# SCH_BMS.net
KiCad netlist of a schematic drawn in Altium Designer
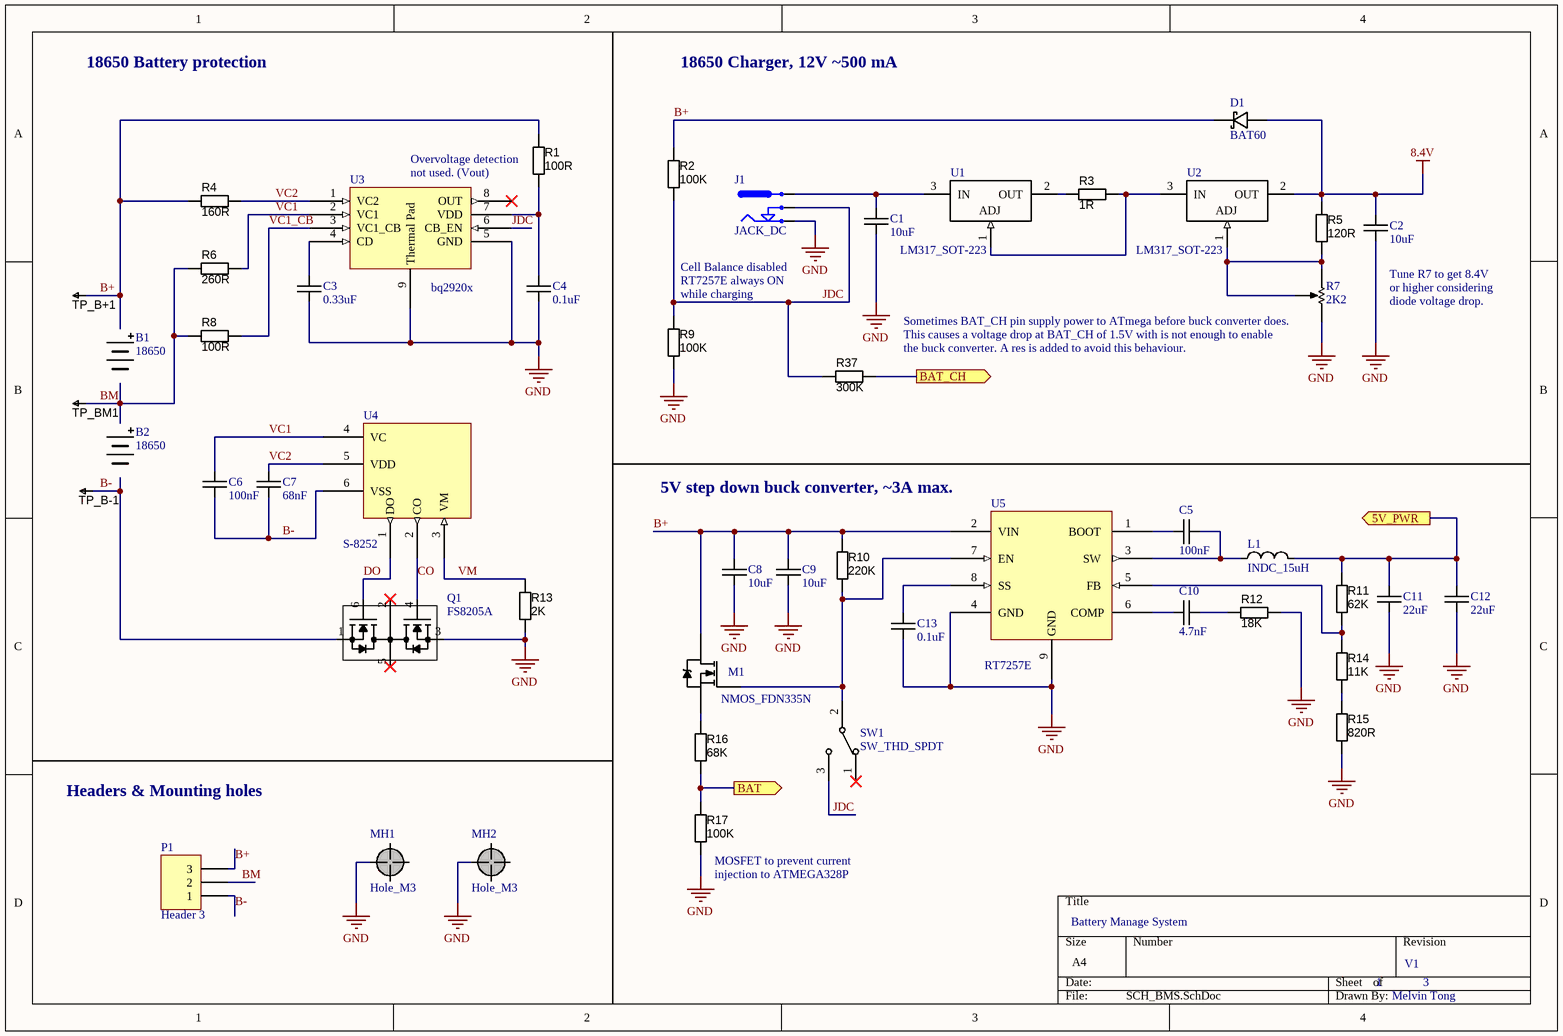
[diagram p0: SCH_BMS.SchDoc]

(export (version "E")
  (design (tool "Eeschema 10.0.6"))
  (components
    (comp (ref "B1") (value "18650") (libsource (lib "Schlib_Sword") (part "Battery_18650")))
    (comp (ref "B2") (value "18650") (libsource (lib "Schlib_Sword") (part "Battery_18650")))
    (comp (ref "C1")
      (value "10uF")
      (footprint "CAP_0805")
      (description "SMD 0805/1206")
      (libsource (lib "Schlib_Sword") (part "CAP_10uF"))
    )
    (comp (ref "C2")
      (value "10uF")
      (footprint "CAP_1206")
      (description "SMD 0805/1206")
      (libsource (lib "Schlib_Sword") (part "CAP_10uF"))
    )
    (comp (ref "C3")
      (value "0.33uF")
      (footprint "CAP_0805")
      (description "SMD 0805")
      (libsource (lib "Schlib_Sword") (part "CAP_330nF"))
    )
    (comp (ref "C4")
      (value "0.1uF")
      (footprint "CAP_0805")
      (description "SMD 0805")
      (libsource (lib "Schlib_Sword") (part "CAP_0.1uF"))
    )
    (comp (ref "C5")
      (value "100nF")
      (footprint "CAP_0805")
      (description "SMD 0805")
      (libsource (lib "Schlib_Sword") (part "CAP_100nF"))
    )
    (comp (ref "C6")
      (value "100nF")
      (footprint "CAP_0805")
      (description "SMD 0805")
      (libsource (lib "Schlib_Sword") (part "CAP_0.1uF"))
    )
    (comp (ref "C7")
      (value "68nF")
      (footprint "CAP_0805")
      (description "SMD 0805")
      (libsource (lib "Schlib_Sword") (part "CAP_0.1uF"))
    )
    (comp (ref "C8")
      (value "10uF")
      (footprint "CAP_1206")
      (description "SMD 0805/1206")
      (libsource (lib "Schlib_Sword") (part "CAP_10uF"))
    )
    (comp (ref "C9")
      (value "10uF")
      (footprint "CAP_1206")
      (description "SMD 0805/1206")
      (libsource (lib "Schlib_Sword") (part "CAP_10uF"))
    )
    (comp (ref "C10")
      (value "4.7nF")
      (footprint "CAP_0805")
      (description "SMD 0805")
      (libsource (lib "Schlib_Sword") (part "CAP_4.7nF"))
    )
    (comp (ref "C11")
      (value "22uF")
      (footprint "CAP_1206")
      (description "SMD 1206")
      (libsource (lib "Schlib_Sword") (part "CAP_22uF"))
    )
    (comp (ref "C12")
      (value "22uF")
      (footprint "CAP_1206")
      (description "SMD 1206")
      (libsource (lib "Schlib_Sword") (part "CAP_22uF"))
    )
    (comp (ref "C13")
      (value "0.1uF")
      (footprint "CAP_0805")
      (description "SMD 0805")
      (libsource (lib "Schlib_Sword") (part "CAP_0.1uF"))
    )
    (comp (ref "D1")
      (value "BAT60")
      (footprint "SOD323")
      (description "Schottky Diode 3A, Vf~0.24V, Vr=10V")
      (libsource (lib "Schlib_Sword") (part "BAT60"))
    )
    (comp (ref "J1") (value "JACK_DC") (footprint "DC-004") (libsource (lib "Schlib_Sword") (part "JACK_DC")))
    (comp (ref "L1")
      (value "INDC_15uH")
      (footprint "IND_15uH")
      (description "15uH ±20% 4.2A 28.4mΩ SMD,12.5x12.5x6.5mm Power Inductors")
      (libsource (lib "Schlib_Sword") (part "INDC_15uH"))
    )
    (comp (ref "M1")
      (value "NMOS_FDN335N")
      (footprint "SOT23_213")
      (libsource (lib "Schlib_Sword") (part "NMOS_FDN335N"))
    )
    (comp (ref "MH1")
      (value "Hole_M3")
      (footprint "Hole_M3")
      (libsource (lib "Schlib_Sword") (part "Hole_M3"))
    )
    (comp (ref "MH2")
      (value "Hole_M3")
      (footprint "Hole_M3")
      (libsource (lib "Schlib_Sword") (part "Hole_M3"))
    )
    (comp (ref "P1")
      (value "Header 3")
      (footprint "HDR1X3")
      (description "Header, 3-Pin")
      (fields (field (name "PUBLISHER") "Altium Limited"))
      (libsource (lib "Miscellaneous Connectors") (part "Header 3"))
    )
    (comp (ref "Q1")
      (value "FS8205A")
      (footprint "SOT23-6")
      (description "NMOS, Drain-Connected, Imax 6A")
      (libsource (lib "Schlib_Sword") (part "FS8205A"))
    )
    (comp (ref "R1")
      (value "100R")
      (footprint "RESC3216X70N")
      (description "Resistor SMD, 1206")
      (libsource (lib "") (part "RES_100R_1"))
    )
    (comp (ref "R2")
      (value "100K")
      (footprint "RESC3216X70N")
      (description "Resistor SMD, 1206")
      (libsource (lib "Schlib_Sword") (part "RES_100K"))
    )
    (comp (ref "R3")
      (value "1R")
      (footprint "RESC6332X70N")
      (description "Resistor SMD 1Ω ±5% 2W ±400ppm/℃ 2512")
      (fields (field (name "TOLERANCE") "±5%") (field (name "Comment") "RES_1R_2512"))
      (libsource (lib "Schlib_Sword") (part "RES_1R_2512"))
    )
    (comp (ref "R4")
      (value "160R")
      (footprint "RESC3216X70N")
      (description "Resistor SMD, 1206")
      (libsource (lib "Schlib_Sword") (part "RES_160R"))
    )
    (comp (ref "R5")
      (value "120R")
      (footprint "RESC3216X70N")
      (description "Resistor SMD, 1206")
      (libsource (lib "Schlib_Sword") (part "RES_120R"))
    )
    (comp (ref "R6")
      (value "260R")
      (footprint "RESC3216X70N")
      (description "Resistor SMD, 1206")
      (libsource (lib "Schlib_Sword") (part "RES_260R"))
    )
    (comp (ref "R7")
      (value "2K2")
      (footprint "RES_VAR")
      (description "Resistor SMD Variable")
      (libsource (lib "Schlib_Sword") (part "RES_Var_2K2"))
    )
    (comp (ref "R8")
      (value "100R")
      (footprint "RESC3216X70N")
      (description "Resistor SMD, 1206")
      (libsource (lib "Schlib_Sword") (part "RES_100R"))
    )
    (comp (ref "R9")
      (value "100K")
      (footprint "RESC3216X70N")
      (description "Resistor SMD, 1206")
      (libsource (lib "Schlib_Sword") (part "RES_100K"))
    )
    (comp (ref "R10")
      (value "220K")
      (footprint "RESC3216X70N")
      (description "Resistor SMD, 1206")
      (libsource (lib "Schlib_Sword") (part "RES_220K"))
    )
    (comp (ref "R11")
      (value "62K")
      (footprint "RESC3216X70N")
      (description "Resistor SMD, 1206")
      (libsource (lib "Schlib_Sword") (part "RES_62K"))
    )
    (comp (ref "R12")
      (value "18K")
      (footprint "RESC3216X70N")
      (description "Resistor SMD, 1206")
      (libsource (lib "Schlib_Sword") (part "RES_18K"))
    )
    (comp (ref "R13")
      (value "2K")
      (footprint "RESC3216X70N")
      (description "Resistor SMD, 1206")
      (libsource (lib "Schlib_Sword") (part "RES_2K"))
    )
    (comp (ref "R14")
      (value "11K")
      (footprint "RESC3216X70N")
      (description "Resistor SMD, 1206")
      (libsource (lib "Schlib_Sword") (part "RES_11K"))
    )
    (comp (ref "R15")
      (value "820R")
      (footprint "RESC3216X70N")
      (description "Resistor SMD, 1206")
      (libsource (lib "Schlib_Sword") (part "RES_820R"))
    )
    (comp (ref "R16")
      (value "68K")
      (footprint "RESC3216X70N")
      (description "Resistor SMD, 1206")
      (libsource (lib "Schlib_Sword") (part "RES_68K"))
    )
    (comp (ref "R17")
      (value "100K")
      (footprint "RESC3216X70N")
      (description "Resistor SMD, 1206")
      (libsource (lib "") (part "RES_100K_1"))
    )
    (comp (ref "R37")
      (value "300K")
      (footprint "RESC3216X70N")
      (description "Resistor SMD, 1206")
      (libsource (lib "Schlib_Sword") (part "RES_300K"))
    )
    (comp (ref "SW1")
      (value "SW_THD_SPDT")
      (footprint "3P_header")
      (description "Switch 2 position")
      (libsource (lib "Schlib_Sword") (part "SW_THD_SPDT"))
    )
    (comp (ref "TP_B+1")
      (value "TESTPOINT")
      (footprint "TP-R20")
      (description "SMD test pin")
      (libsource (lib "Schlib_Sword") (part "TESTPOINT"))
    )
    (comp (ref "TP_B-1")
      (value "TESTPOINT")
      (footprint "TP-R20")
      (description "SMD test pin")
      (libsource (lib "Schlib_Sword") (part "TESTPOINT"))
    )
    (comp (ref "TP_BM1")
      (value "TESTPOINT")
      (footprint "TP-R20")
      (description "SMD test pin")
      (libsource (lib "Schlib_Sword") (part "TESTPOINT"))
    )
    (comp (ref "U1")
      (value "LM317_SOT-223")
      (footprint "SOT223")
      (description "Linear Voltage Regulator")
      (libsource (lib "Schlib_Sword") (part "LM317_SOT-223"))
    )
    (comp (ref "U2")
      (value "LM317_SOT-223")
      (footprint "SOT223")
      (description "Linear Voltage Regulator")
      (libsource (lib "Schlib_Sword") (part "LM317_SOT-223"))
    )
    (comp (ref "U3")
      (value "bq2920x")
      (footprint "bq2920x")
      (description "Automatic Cell Balance 2S Li-Ion Battery")
      (libsource (lib "Schlib_Sword") (part "bq2920x"))
    )
    (comp (ref "U4")
      (value "S-8252")
      (footprint "SOT23-6")
      (description "Battery protection IC for 2S battery pack")
      (libsource (lib "Schlib_Sword") (part "S-8252"))
    )
    (comp (ref "U5")
      (value "RT7257E")
      (footprint "RT7257E")
      (description "DC/DC Buck Converter, 3A, 4.5V-17V Vin")
      (libsource (lib "Schlib_Sword") (part "RT7257E"))
    )
  )
  (nets
    (net (code "1") (name "/5V_PWR") (class "Default")
      (node (ref "C11") (pin "1") (pintype "passive"))
      (node (ref "C12") (pin "1") (pintype "passive"))
      (node (ref "L1") (pin "2") (pinfunction "2_2") (pintype "passive"))
      (node (ref "R11") (pin "1") (pinfunction "1_1") (pintype "passive"))
    )
    (net (code "2") (name "/B+") (class "Default")
      (node (ref "C8") (pin "1") (pintype "passive"))
      (node (ref "C9") (pin "1") (pintype "passive"))
      (node (ref "D1") (pin "K") (pinfunction "K_K") (pintype "passive"))
      (node (ref "M1") (pin "3") (pinfunction "D_3") (pintype "passive"))
      (node (ref "P1") (pin "3") (pinfunction "3_3") (pintype "passive"))
      (node (ref "R1") (pin "2") (pinfunction "2_2") (pintype "passive"))
      (node (ref "R10") (pin "1") (pinfunction "1_1") (pintype "passive"))
      (node (ref "R2") (pin "2") (pinfunction "2_2") (pintype "passive"))
      (node (ref "R4") (pin "1") (pinfunction "1_1") (pintype "passive"))
      (node (ref "TP_B+1") (pin "1") (pintype "passive"))
      (node (ref "U5") (pin "2") (pinfunction "VIN_2") (pintype "power_in"))
    )
    (net (code "3") (name "/B-") (class "Default")
      (node (ref "C6") (pin "2") (pintype "passive"))
      (node (ref "C7") (pin "2") (pintype "passive"))
      (node (ref "P1") (pin "1") (pinfunction "1_1") (pintype "passive"))
      (node (ref "Q1") (pin "1") (pinfunction "S1_1") (pintype "passive"))
      (node (ref "TP_B-1") (pin "1") (pintype "passive"))
      (node (ref "U4") (pin "6") (pinfunction "VSS_6") (pintype "power_in"))
    )
    (net (code "4") (name "/BAT") (class "Default")
      (node (ref "R16") (pin "2") (pinfunction "2_2") (pintype "passive"))
      (node (ref "R17") (pin "1") (pinfunction "1_1") (pintype "passive"))
    )
    (net (code "5") (name "/BAT_CH") (class "Default")
      (node (ref "R37") (pin "2") (pinfunction "2_2") (pintype "passive"))
    )
    (net (code "6") (name "/BM") (class "Default")
      (node (ref "P1") (pin "2") (pinfunction "2_2") (pintype "passive"))
      (node (ref "R6") (pin "1") (pinfunction "1_1") (pintype "passive"))
      (node (ref "R8") (pin "1") (pinfunction "1_1") (pintype "passive"))
      (node (ref "TP_BM1") (pin "1") (pintype "passive"))
    )
    (net (code "7") (name "/CO") (class "Default")
      (node (ref "Q1") (pin "4") (pinfunction "G2_4") (pintype "passive"))
      (node (ref "U4") (pin "2") (pinfunction "CO_2") (pintype "output"))
    )
    (net (code "8") (name "/DO") (class "Default")
      (node (ref "Q1") (pin "6") (pinfunction "G1_6") (pintype "passive"))
      (node (ref "U4") (pin "1") (pinfunction "DO_1") (pintype "output"))
    )
    (net (code "9") (name "/JDC") (class "Default")
      (node (ref "J1") (pin "3") (pinfunction "3_3") (pintype "passive"))
      (node (ref "R2") (pin "1") (pinfunction "1_1") (pintype "passive"))
      (node (ref "R37") (pin "1") (pinfunction "1_1") (pintype "passive"))
      (node (ref "R9") (pin "2") (pinfunction "2_2") (pintype "passive"))
      (node (ref "SW1") (pin "3") (pinfunction "3_3") (pintype "passive"))
      (node (ref "U3") (pin "6") (pinfunction "CB_EN_6") (pintype "input"))
    )
    (net (code "10") (name "/VC1") (class "Default")
      (node (ref "C6") (pin "1") (pintype "passive"))
      (node (ref "R6") (pin "2") (pinfunction "2_2") (pintype "passive"))
      (node (ref "U3") (pin "2") (pinfunction "VC1_2") (pintype "input"))
      (node (ref "U4") (pin "4") (pinfunction "VC_4") (pintype "power_in"))
    )
    (net (code "11") (name "/VC1_CB") (class "Default")
      (node (ref "R8") (pin "2") (pinfunction "2_2") (pintype "passive"))
      (node (ref "U3") (pin "3") (pinfunction "VC1_CB_3") (pintype "input"))
    )
    (net (code "12") (name "/VC2") (class "Default")
      (node (ref "C7") (pin "1") (pintype "passive"))
      (node (ref "R4") (pin "2") (pinfunction "2_2") (pintype "passive"))
      (node (ref "U3") (pin "1") (pinfunction "VC2_1") (pintype "input"))
      (node (ref "U4") (pin "5") (pinfunction "VDD_5") (pintype "power_in"))
    )
    (net (code "13") (name "/VM") (class "Default")
      (node (ref "R13") (pin "1") (pinfunction "1_1") (pintype "passive"))
      (node (ref "U4") (pin "3") (pinfunction "_VM_3") (pintype "input"))
    )
    (net (code "14") (name "8.4V") (class "Default")
      (node (ref "C2") (pin "1") (pintype "passive"))
      (node (ref "D1") (pin "A") (pinfunction "A_A") (pintype "passive"))
      (node (ref "R5") (pin "1") (pinfunction "1_1") (pintype "passive"))
      (node (ref "U2") (pin "2") (pinfunction "OUT_2") (pintype "power_in"))
    )
    (net (code "15") (name "GND") (class "Default")
      (node (ref "C1") (pin "2") (pintype "passive"))
      (node (ref "C11") (pin "2") (pintype "passive"))
      (node (ref "C12") (pin "2") (pintype "passive"))
      (node (ref "C13") (pin "2") (pintype "passive"))
      (node (ref "C2") (pin "2") (pintype "passive"))
      (node (ref "C3") (pin "2") (pintype "passive"))
      (node (ref "C4") (pin "2") (pintype "passive"))
      (node (ref "C8") (pin "2") (pintype "passive"))
      (node (ref "C9") (pin "2") (pintype "passive"))
      (node (ref "J1") (pin "1") (pinfunction "1_1") (pintype "passive"))
      (node (ref "MH1") (pin "MH") (pinfunction "MH_MH") (pintype "passive"))
      (node (ref "MH2") (pin "MH") (pinfunction "MH_MH") (pintype "passive"))
      (node (ref "Q1") (pin "3") (pinfunction "D2_3") (pintype "passive"))
      (node (ref "R12") (pin "2") (pinfunction "2_2") (pintype "passive"))
      (node (ref "R13") (pin "2") (pinfunction "2_2") (pintype "passive"))
      (node (ref "R15") (pin "2") (pinfunction "2_2") (pintype "passive"))
      (node (ref "R17") (pin "2") (pinfunction "2_2") (pintype "passive"))
      (node (ref "R7") (pin "3") (pinfunction "CW_3") (pintype "passive"))
      (node (ref "R9") (pin "1") (pinfunction "1_1") (pintype "passive"))
      (node (ref "U3") (pin "5") (pinfunction "GND_5") (pintype "power_in"))
      (node (ref "U3") (pin "9") (pinfunction "Thermal_Pad_9") (pintype "power_in"))
      (node (ref "U5") (pin "4") (pinfunction "GND_4") (pintype "power_in"))
      (node (ref "U5") (pin "9") (pinfunction "GND_9") (pintype "power_in"))
    )
    (net (code "16") (name "Net-(C10-Pad2)") (class "Default")
      (node (ref "C10") (pin "2") (pintype "passive"))
      (node (ref "R12") (pin "1") (pinfunction "1_1") (pintype "passive"))
    )
    (net (code "17") (name "Net-(M1-G)") (class "Default")
      (node (ref "M1") (pin "1") (pinfunction "G_1") (pintype "passive"))
      (node (ref "R10") (pin "2") (pinfunction "2_2") (pintype "passive"))
      (node (ref "SW1") (pin "2") (pinfunction "2_2") (pintype "passive"))
      (node (ref "U5") (pin "7") (pinfunction "EN_7") (pintype "input"))
    )
    (net (code "18") (name "Net-(M1-S)") (class "Default")
      (node (ref "M1") (pin "2") (pinfunction "S_2") (pintype "passive"))
      (node (ref "R16") (pin "1") (pinfunction "1_1") (pintype "passive"))
    )
    (net (code "19") (name "Net-(R7-CCW)") (class "Default")
      (node (ref "R5") (pin "2") (pinfunction "2_2") (pintype "passive"))
      (node (ref "R7") (pin "1") (pinfunction "CCW_1") (pintype "passive"))
      (node (ref "R7") (pin "2") (pinfunction "WIPER_2") (pintype "passive"))
      (node (ref "U2") (pin "1") (pinfunction "ADJ_1") (pintype "input"))
    )
    (net (code "20") (name "Net-(R14-Pad2)") (class "Default")
      (node (ref "R14") (pin "2") (pinfunction "2_2") (pintype "passive"))
      (node (ref "R15") (pin "1") (pinfunction "1_1") (pintype "passive"))
    )
    (net (code "21") (name "Net-(U1-ADJ)") (class "Default")
      (node (ref "R3") (pin "2") (pinfunction "2_2") (pintype "passive"))
      (node (ref "U1") (pin "1") (pinfunction "ADJ_1") (pintype "input"))
      (node (ref "U2") (pin "3") (pinfunction "IN_3") (pintype "power_in"))
    )
    (net (code "22") (name "Net-(U1-IN)") (class "Default")
      (node (ref "C1") (pin "1") (pintype "passive"))
      (node (ref "J1") (pin "2") (pinfunction "2_2") (pintype "passive"))
      (node (ref "U1") (pin "3") (pinfunction "IN_3") (pintype "power_in"))
    )
    (net (code "23") (name "Net-(U1-OUT)") (class "Default")
      (node (ref "R3") (pin "1") (pinfunction "1_1") (pintype "passive"))
      (node (ref "U1") (pin "2") (pinfunction "OUT_2") (pintype "power_in"))
    )
    (net (code "24") (name "Net-(U3-CD)") (class "Default")
      (node (ref "C3") (pin "1") (pintype "passive"))
      (node (ref "U3") (pin "4") (pinfunction "CD_4") (pintype "input"))
    )
    (net (code "25") (name "Net-(U3-VDD)") (class "Default")
      (node (ref "C4") (pin "1") (pintype "passive"))
      (node (ref "R1") (pin "1") (pinfunction "1_1") (pintype "passive"))
      (node (ref "U3") (pin "7") (pinfunction "VDD_7") (pintype "power_in"))
    )
    (net (code "26") (name "Net-(U5-BOOT)") (class "Default")
      (node (ref "C5") (pin "1") (pintype "passive"))
      (node (ref "U5") (pin "1") (pinfunction "BOOT_1") (pintype "passive"))
    )
    (net (code "27") (name "Net-(U5-COMP)") (class "Default")
      (node (ref "C10") (pin "1") (pintype "passive"))
      (node (ref "U5") (pin "6") (pinfunction "COMP_6") (pintype "passive"))
    )
    (net (code "28") (name "Net-(U5-FB)") (class "Default")
      (node (ref "R11") (pin "2") (pinfunction "2_2") (pintype "passive"))
      (node (ref "R14") (pin "1") (pinfunction "1_1") (pintype "passive"))
      (node (ref "U5") (pin "5") (pinfunction "FB_5") (pintype "input"))
    )
    (net (code "29") (name "Net-(U5-SS)") (class "Default")
      (node (ref "C13") (pin "1") (pintype "passive"))
      (node (ref "U5") (pin "8") (pinfunction "SS_8") (pintype "input"))
    )
    (net (code "30") (name "Net-(U5-SW)") (class "Default")
      (node (ref "C5") (pin "2") (pintype "passive"))
      (node (ref "L1") (pin "1") (pinfunction "1_1") (pintype "passive"))
      (node (ref "U5") (pin "3") (pinfunction "SW_3") (pintype "output"))
    )
    (net (code "31") (name "unconnected-(Q1-D1-Pad2)") (class "Default")
      (node (ref "Q1") (pin "2") (pinfunction "D1_2") (pintype "passive+no_connect"))
    )
    (net (code "32") (name "unconnected-(Q1-D2-Pad5)") (class "Default")
      (node (ref "Q1") (pin "5") (pinfunction "D2_5") (pintype "passive+no_connect"))
    )
    (net (code "33") (name "unconnected-(SW1-Pad1)") (class "Default")
      (node (ref "SW1") (pin "1") (pinfunction "1_1") (pintype "passive+no_connect"))
    )
    (net (code "34") (name "unconnected-(U3-OUT-Pad8)") (class "Default")
      (node (ref "U3") (pin "8") (pinfunction "OUT_8") (pintype "output+no_connect"))
    )
  )
)
